# esq.net
KiCad netlist of a schematic drawn in Altium Designer
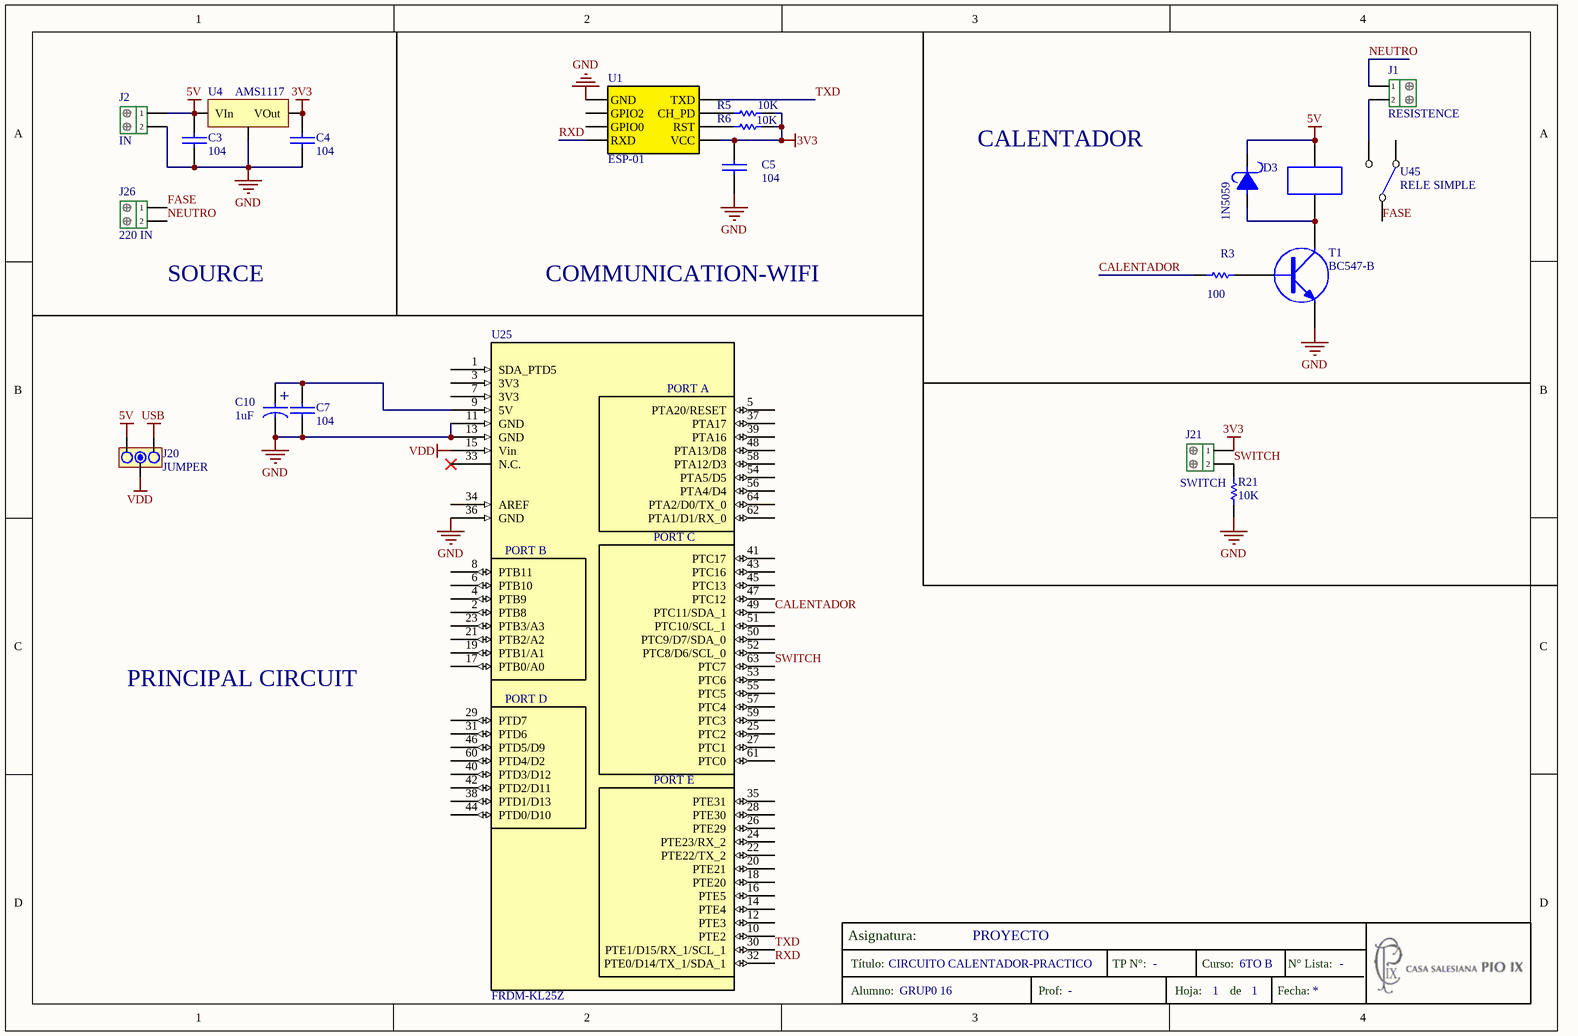
[diagram p0: esq.SchDoc]

(export (version "E")
  (design (tool "Eeschema 10.0.6"))
  (components
    (comp (ref "C3")
      (value "104")
      (footprint "0805")
      (description "cap")
      (fields (field (name "AUTOR") "Guido Spataro"))
      (libsource (lib "Schlib1") (part "CAP"))
    )
    (comp (ref "C4")
      (value "104")
      (footprint "1206")
      (description "cap")
      (fields (field (name "AUTOR") "Guido Spataro"))
      (libsource (lib "Schlib") (part "CAP"))
    )
    (comp (ref "C5")
      (value "104")
      (footprint "0805")
      (description "cap")
      (fields (field (name "AUTOR") "Guido Spataro"))
      (libsource (lib "scdlib") (part "CAP"))
    )
    (comp (ref "C7")
      (value "104")
      (footprint "0805")
      (description "cap")
      (fields (field (name "AUTOR") "Guido Spataro"))
      (libsource (lib "scdlib") (part "CAP"))
    )
    (comp (ref "C10")
      (value "1uF")
      (footprint "CAP100RP")
      (description "Cap polarizado")
      (libsource (lib "Schlib") (part "CAPPOL"))
    )
    (comp (ref "D3")
      (value "1N5059")
      (footprint "Diodo")
      (description "Diodo")
      (fields (field (name "AUTOR") "Guido Spataro"))
      (libsource (lib "Schlib1") (part "DIODO SCHOTTKY"))
    )
    (comp (ref "J1")
      (value "RESISTENCE")
      (footprint "BORNERA2")
      (description "Bornera de 2 pines")
      (fields (field (name "AUTOR") "Guido Spataro"))
      (libsource (lib "Schlib1") (part "Bornera_2"))
    )
    (comp (ref "J2")
      (value "IN")
      (footprint "BORNERA2")
      (description "Bornera de 2 pines")
      (fields (field (name "AUTOR") "Guido Spataro"))
      (libsource (lib "") (part "Bornera_2_1"))
    )
    (comp (ref "J20") (value "JUMPER") (footprint "JUMPER3") (libsource (lib "scdlib") (part "JUMPER3")))
    (comp (ref "J21")
      (value "SWITCH")
      (footprint "BORNERA2")
      (description "Bornera de 2 pines")
      (fields (field (name "AUTOR") "Guido Spataro"))
      (libsource (lib "") (part "Bornera_2_1"))
    )
    (comp (ref "J26")
      (value "220 IN")
      (footprint "BORNERA2")
      (description "Bornera de 2 pines")
      (fields (field (name "AUTOR") "Guido Spataro"))
      (libsource (lib "") (part "Bornera_2_1"))
    )
    (comp (ref "R3")
      (value "100")
      (footprint "0805")
      (description "Resistencia")
      (fields (field (name "AUTOR") "Guido Spataro"))
      (libsource (lib "Schlib1") (part "RES"))
    )
    (comp (ref "R5")
      (value "10K")
      (footprint "0805")
      (description "Resistencia")
      (fields (field (name "AUTOR") "Guido Spataro"))
      (libsource (lib "scdlib") (part "RES"))
    )
    (comp (ref "R6")
      (value "10K")
      (footprint "0805")
      (description "Resistencia")
      (fields (field (name "AUTOR") "Guido Spataro"))
      (libsource (lib "scdlib") (part "RES"))
    )
    (comp (ref "R21")
      (value "10K")
      (footprint "0805")
      (description "Resistencia")
      (fields (field (name "AUTOR") "Guido Spataro"))
      (libsource (lib "Schlib1") (part "RES"))
    )
    (comp (ref "T1")
      (value "BC547-B")
      (footprint "SOT23")
      (libsource (lib "Schlib1") (part "TRANSISTOR NPN"))
    )
    (comp (ref "U1") (value "ESP-01") (footprint "ESP-01") (libsource (lib "Schlib") (part "ESP-01")))
    (comp (ref "U4") (value "AMS1117") (footprint "AMS1117") (libsource (lib "Schlib") (part "AMS1117")))
    (comp (ref "U25")
      (value "FRDM-KL25Z")
      (footprint "MICRO")
      (fields (field (name "AUTOR") "Guido Spataro"))
      (libsource (lib "Schlib") (part "FRDM-KL25Z"))
    )
    (comp (ref "U45")
      (value "RELE SIMPLE")
      (footprint "RELE SERIE 943")
      (libsource (lib "Schlib1") (part "RELE SIMPLE"))
    )
  )
  (nets
    (net (code "1") (name "/CALENTADOR") (class "Default")
      (node (ref "R3") (pin "2") (pinfunction "2_2") (pintype "passive"))
      (node (ref "U25") (pin "49") (pinfunction "PTC11/SDA_1_49") (pintype "bidirectional"))
    )
    (net (code "2") (name "/FASE") (class "Default")
      (node (ref "J26") (pin "1") (pinfunction "1_1") (pintype "passive"))
      (node (ref "U45") (pin "C1") (pinfunction "C1_C1") (pintype "passive"))
    )
    (net (code "3") (name "/NEUTRO") (class "Default")
      (node (ref "J1") (pin "1") (pinfunction "1_1") (pintype "passive"))
      (node (ref "J26") (pin "2") (pinfunction "2_2") (pintype "passive"))
    )
    (net (code "4") (name "/RXD") (class "Default")
      (node (ref "U1") (pin "4") (pinfunction "RXD_4") (pintype "passive"))
      (node (ref "U25") (pin "32") (pinfunction "PTE0/D14/TX_1/SDA_1_32") (pintype "bidirectional"))
    )
    (net (code "5") (name "/SWITCH") (class "Default")
      (node (ref "J21") (pin "2") (pinfunction "2_2") (pintype "passive"))
      (node (ref "R21") (pin "1") (pinfunction "1_1") (pintype "passive"))
      (node (ref "U25") (pin "63") (pinfunction "PTC7_63") (pintype "bidirectional"))
    )
    (net (code "6") (name "/TXD") (class "Default")
      (node (ref "U1") (pin "5") (pinfunction "TXD_5") (pintype "passive"))
      (node (ref "U25") (pin "30") (pinfunction "PTE1/D15/RX_1/SCL_1_30") (pintype "bidirectional"))
    )
    (net (code "7") (name "3V3") (class "Default")
      (node (ref "C4") (pin "1") (pinfunction "1_1") (pintype "passive"))
      (node (ref "C5") (pin "2") (pinfunction "2_2") (pintype "passive"))
      (node (ref "J21") (pin "1") (pinfunction "1_1") (pintype "passive"))
      (node (ref "R5") (pin "1") (pinfunction "1_1") (pintype "passive"))
      (node (ref "R6") (pin "1") (pinfunction "1_1") (pintype "passive"))
      (node (ref "U1") (pin "8") (pinfunction "VCC_8") (pintype "passive"))
      (node (ref "U4") (pin "3") (pinfunction "VOut_3") (pintype "passive"))
    )
    (net (code "8") (name "5V") (class "Default")
      (node (ref "C3") (pin "1") (pinfunction "1_1") (pintype "passive"))
      (node (ref "D3") (pin "2") (pinfunction "2_2") (pintype "passive"))
      (node (ref "J2") (pin "1") (pinfunction "1_1") (pintype "passive"))
      (node (ref "J20") (pin "1") (pinfunction "1_1") (pintype "passive"))
      (node (ref "U4") (pin "1") (pinfunction "VIn_1") (pintype "passive"))
      (node (ref "U45") (pin "B1") (pinfunction "B1_B1") (pintype "passive"))
    )
    (net (code "9") (name "GND") (class "Default")
      (node (ref "C10") (pin "2") (pinfunction "2_2") (pintype "passive"))
      (node (ref "C3") (pin "2") (pinfunction "2_2") (pintype "passive"))
      (node (ref "C4") (pin "2") (pinfunction "2_2") (pintype "passive"))
      (node (ref "C5") (pin "1") (pinfunction "1_1") (pintype "passive"))
      (node (ref "C7") (pin "1") (pinfunction "1_1") (pintype "passive"))
      (node (ref "J2") (pin "2") (pinfunction "2_2") (pintype "passive"))
      (node (ref "R21") (pin "2") (pinfunction "2_2") (pintype "passive"))
      (node (ref "T1") (pin "3") (pinfunction "E_3") (pintype "passive"))
      (node (ref "U1") (pin "1") (pinfunction "GND_1") (pintype "passive"))
      (node (ref "U25") (pin "11") (pinfunction "GND_11") (pintype "input"))
      (node (ref "U25") (pin "13") (pinfunction "GND_13") (pintype "input"))
      (node (ref "U25") (pin "36") (pinfunction "GND_36") (pintype "input"))
      (node (ref "U4") (pin "2") (pinfunction "GND_2") (pintype "passive"))
    )
    (net (code "10") (name "Net-(J1-Pad2)") (class "Default")
      (node (ref "J1") (pin "2") (pinfunction "2_2") (pintype "passive"))
      (node (ref "U45") (pin "NA1") (pinfunction "NA1_NA1") (pintype "passive"))
    )
    (net (code "11") (name "Net-(T1-B)") (class "Default")
      (node (ref "R3") (pin "1") (pinfunction "1_1") (pintype "passive"))
      (node (ref "T1") (pin "1") (pinfunction "B_1") (pintype "passive"))
    )
    (net (code "12") (name "Net-(T1-C)") (class "Default")
      (node (ref "D3") (pin "1") (pinfunction "1_1") (pintype "passive"))
      (node (ref "T1") (pin "2") (pinfunction "C_2") (pintype "passive"))
      (node (ref "U45") (pin "B2") (pinfunction "B2_B2") (pintype "passive"))
    )
    (net (code "13") (name "Net-(U1-CH_PD)") (class "Default")
      (node (ref "R5") (pin "2") (pinfunction "2_2") (pintype "passive"))
      (node (ref "U1") (pin "6") (pinfunction "CH_PD_6") (pintype "passive"))
    )
    (net (code "14") (name "Net-(U1-RST)") (class "Default")
      (node (ref "R6") (pin "2") (pinfunction "2_2") (pintype "passive"))
      (node (ref "U1") (pin "7") (pinfunction "RST_7") (pintype "passive"))
    )
    (net (code "15") (name "Net-(U25-5V)") (class "Default")
      (node (ref "C10") (pin "1") (pinfunction "1_1") (pintype "passive"))
      (node (ref "C7") (pin "2") (pinfunction "2_2") (pintype "passive"))
      (node (ref "U25") (pin "9") (pinfunction "5V_9") (pintype "input"))
    )
    (net (code "16") (name "USB") (class "Default")
      (node (ref "J20") (pin "3") (pinfunction "3_3") (pintype "passive"))
    )
    (net (code "17") (name "VDD") (class "Default")
      (node (ref "J20") (pin "2") (pinfunction "2_2") (pintype "passive"))
      (node (ref "U25") (pin "15") (pinfunction "Vin_15") (pintype "input"))
    )
    (net (code "18") (name "unconnected-(U1-GPIO0-Pad3)") (class "Default")
      (node (ref "U1") (pin "3") (pinfunction "GPIO0_3") (pintype "passive"))
    )
    (net (code "19") (name "unconnected-(U1-GPIO2-Pad2)") (class "Default")
      (node (ref "U1") (pin "2") (pinfunction "GPIO2_2") (pintype "passive"))
    )
    (net (code "20") (name "unconnected-(U25-3V3-Pad3)") (class "Default")
      (node (ref "U25") (pin "3") (pinfunction "3V3_3") (pintype "input"))
    )
    (net (code "21") (name "unconnected-(U25-3V3-Pad7)") (class "Default")
      (node (ref "U25") (pin "7") (pinfunction "3V3_7") (pintype "input"))
    )
    (net (code "22") (name "unconnected-(U25-AREF-Pad34)") (class "Default")
      (node (ref "U25") (pin "34") (pinfunction "AREF_34") (pintype "input"))
    )
    (net (code "23") (name "unconnected-(U25-N.C.-Pad33)") (class "Default")
      (node (ref "U25") (pin "33") (pinfunction "N.C._33") (pintype "open_emitter+no_connect"))
    )
    (net (code "24") (name "unconnected-(U25-PTA1{slash}D1{slash}RX_0-Pad62)") (class "Default")
      (node (ref "U25") (pin "62") (pinfunction "PTA1/D1/RX_0_62") (pintype "bidirectional"))
    )
    (net (code "25") (name "unconnected-(U25-PTA2{slash}D0{slash}TX_0-Pad64)") (class "Default")
      (node (ref "U25") (pin "64") (pinfunction "PTA2/D0/TX_0_64") (pintype "bidirectional"))
    )
    (net (code "26") (name "unconnected-(U25-PTA4{slash}D4-Pad56)") (class "Default")
      (node (ref "U25") (pin "56") (pinfunction "PTA4/D4_56") (pintype "bidirectional"))
    )
    (net (code "27") (name "unconnected-(U25-PTA5{slash}D5-Pad54)") (class "Default")
      (node (ref "U25") (pin "54") (pinfunction "PTA5/D5_54") (pintype "bidirectional"))
    )
    (net (code "28") (name "unconnected-(U25-PTA12{slash}D3-Pad58)") (class "Default")
      (node (ref "U25") (pin "58") (pinfunction "PTA12/D3_58") (pintype "bidirectional"))
    )
    (net (code "29") (name "unconnected-(U25-PTA13{slash}D8-Pad48)") (class "Default")
      (node (ref "U25") (pin "48") (pinfunction "PTA13/D8_48") (pintype "bidirectional"))
    )
    (net (code "30") (name "unconnected-(U25-PTA16-Pad39)") (class "Default")
      (node (ref "U25") (pin "39") (pinfunction "PTA16_39") (pintype "bidirectional"))
    )
    (net (code "31") (name "unconnected-(U25-PTA17-Pad37)") (class "Default")
      (node (ref "U25") (pin "37") (pinfunction "PTA17_37") (pintype "bidirectional"))
    )
    (net (code "32") (name "unconnected-(U25-PTA20{slash}RESET-Pad5)") (class "Default")
      (node (ref "U25") (pin "5") (pinfunction "PTA20/RESET_5") (pintype "bidirectional"))
    )
    (net (code "33") (name "unconnected-(U25-PTB0{slash}A0-Pad17)") (class "Default")
      (node (ref "U25") (pin "17") (pinfunction "PTB0/A0_17") (pintype "bidirectional"))
    )
    (net (code "34") (name "unconnected-(U25-PTB1{slash}A1-Pad19)") (class "Default")
      (node (ref "U25") (pin "19") (pinfunction "PTB1/A1_19") (pintype "bidirectional"))
    )
    (net (code "35") (name "unconnected-(U25-PTB2{slash}A2-Pad21)") (class "Default")
      (node (ref "U25") (pin "21") (pinfunction "PTB2/A2_21") (pintype "bidirectional"))
    )
    (net (code "36") (name "unconnected-(U25-PTB3{slash}A3-Pad23)") (class "Default")
      (node (ref "U25") (pin "23") (pinfunction "PTB3/A3_23") (pintype "bidirectional"))
    )
    (net (code "37") (name "unconnected-(U25-PTB8-Pad2)") (class "Default")
      (node (ref "U25") (pin "2") (pinfunction "PTB8_2") (pintype "bidirectional"))
    )
    (net (code "38") (name "unconnected-(U25-PTB9-Pad4)") (class "Default")
      (node (ref "U25") (pin "4") (pinfunction "PTB9_4") (pintype "bidirectional"))
    )
    (net (code "39") (name "unconnected-(U25-PTB10-Pad6)") (class "Default")
      (node (ref "U25") (pin "6") (pinfunction "PTB10_6") (pintype "bidirectional"))
    )
    (net (code "40") (name "unconnected-(U25-PTB11-Pad8)") (class "Default")
      (node (ref "U25") (pin "8") (pinfunction "PTB11_8") (pintype "bidirectional"))
    )
    (net (code "41") (name "unconnected-(U25-PTC0-Pad61)") (class "Default")
      (node (ref "U25") (pin "61") (pinfunction "PTC0_61") (pintype "bidirectional"))
    )
    (net (code "42") (name "unconnected-(U25-PTC1-Pad27)") (class "Default")
      (node (ref "U25") (pin "27") (pinfunction "PTC1_27") (pintype "bidirectional"))
    )
    (net (code "43") (name "unconnected-(U25-PTC2-Pad25)") (class "Default")
      (node (ref "U25") (pin "25") (pinfunction "PTC2_25") (pintype "bidirectional"))
    )
    (net (code "44") (name "unconnected-(U25-PTC3-Pad59)") (class "Default")
      (node (ref "U25") (pin "59") (pinfunction "PTC3_59") (pintype "bidirectional"))
    )
    (net (code "45") (name "unconnected-(U25-PTC4-Pad57)") (class "Default")
      (node (ref "U25") (pin "57") (pinfunction "PTC4_57") (pintype "bidirectional"))
    )
    (net (code "46") (name "unconnected-(U25-PTC5-Pad55)") (class "Default")
      (node (ref "U25") (pin "55") (pinfunction "PTC5_55") (pintype "bidirectional"))
    )
    (net (code "47") (name "unconnected-(U25-PTC6-Pad53)") (class "Default")
      (node (ref "U25") (pin "53") (pinfunction "PTC6_53") (pintype "bidirectional"))
    )
    (net (code "48") (name "unconnected-(U25-PTC8{slash}D6{slash}SCL_0-Pad52)") (class "Default")
      (node (ref "U25") (pin "52") (pinfunction "PTC8/D6/SCL_0_52") (pintype "bidirectional"))
    )
    (net (code "49") (name "unconnected-(U25-PTC9{slash}D7{slash}SDA_0-Pad50)") (class "Default")
      (node (ref "U25") (pin "50") (pinfunction "PTC9/D7/SDA_0_50") (pintype "bidirectional"))
    )
    (net (code "50") (name "unconnected-(U25-PTC10{slash}SCL_1-Pad51)") (class "Default")
      (node (ref "U25") (pin "51") (pinfunction "PTC10/SCL_1_51") (pintype "bidirectional"))
    )
    (net (code "51") (name "unconnected-(U25-PTC12-Pad47)") (class "Default")
      (node (ref "U25") (pin "47") (pinfunction "PTC12_47") (pintype "bidirectional"))
    )
    (net (code "52") (name "unconnected-(U25-PTC13-Pad45)") (class "Default")
      (node (ref "U25") (pin "45") (pinfunction "PTC13_45") (pintype "bidirectional"))
    )
    (net (code "53") (name "unconnected-(U25-PTC16-Pad43)") (class "Default")
      (node (ref "U25") (pin "43") (pinfunction "PTC16_43") (pintype "bidirectional"))
    )
    (net (code "54") (name "unconnected-(U25-PTC17-Pad41)") (class "Default")
      (node (ref "U25") (pin "41") (pinfunction "PTC17_41") (pintype "bidirectional"))
    )
    (net (code "55") (name "unconnected-(U25-PTD0{slash}D10-Pad44)") (class "Default")
      (node (ref "U25") (pin "44") (pinfunction "PTD0/D10_44") (pintype "bidirectional"))
    )
    (net (code "56") (name "unconnected-(U25-PTD1{slash}D13-Pad38)") (class "Default")
      (node (ref "U25") (pin "38") (pinfunction "PTD1/D13_38") (pintype "bidirectional"))
    )
    (net (code "57") (name "unconnected-(U25-PTD2{slash}D11-Pad42)") (class "Default")
      (node (ref "U25") (pin "42") (pinfunction "PTD2/D11_42") (pintype "bidirectional"))
    )
    (net (code "58") (name "unconnected-(U25-PTD3{slash}D12-Pad40)") (class "Default")
      (node (ref "U25") (pin "40") (pinfunction "PTD3/D12_40") (pintype "bidirectional"))
    )
    (net (code "59") (name "unconnected-(U25-PTD4{slash}D2-Pad60)") (class "Default")
      (node (ref "U25") (pin "60") (pinfunction "PTD4/D2_60") (pintype "bidirectional"))
    )
    (net (code "60") (name "unconnected-(U25-PTD5{slash}D9-Pad46)") (class "Default")
      (node (ref "U25") (pin "46") (pinfunction "PTD5/D9_46") (pintype "bidirectional"))
    )
    (net (code "61") (name "unconnected-(U25-PTD6-Pad31)") (class "Default")
      (node (ref "U25") (pin "31") (pinfunction "PTD6_31") (pintype "bidirectional"))
    )
    (net (code "62") (name "unconnected-(U25-PTD7-Pad29)") (class "Default")
      (node (ref "U25") (pin "29") (pinfunction "PTD7_29") (pintype "bidirectional"))
    )
    (net (code "63") (name "unconnected-(U25-PTE2-Pad10)") (class "Default")
      (node (ref "U25") (pin "10") (pinfunction "PTE2_10") (pintype "bidirectional"))
    )
    (net (code "64") (name "unconnected-(U25-PTE3-Pad12)") (class "Default")
      (node (ref "U25") (pin "12") (pinfunction "PTE3_12") (pintype "bidirectional"))
    )
    (net (code "65") (name "unconnected-(U25-PTE4-Pad14)") (class "Default")
      (node (ref "U25") (pin "14") (pinfunction "PTE4_14") (pintype "bidirectional"))
    )
    (net (code "66") (name "unconnected-(U25-PTE5-Pad16)") (class "Default")
      (node (ref "U25") (pin "16") (pinfunction "PTE5_16") (pintype "bidirectional"))
    )
    (net (code "67") (name "unconnected-(U25-PTE20-Pad18)") (class "Default")
      (node (ref "U25") (pin "18") (pinfunction "PTE20_18") (pintype "bidirectional"))
    )
    (net (code "68") (name "unconnected-(U25-PTE21-Pad20)") (class "Default")
      (node (ref "U25") (pin "20") (pinfunction "PTE21_20") (pintype "bidirectional"))
    )
    (net (code "69") (name "unconnected-(U25-PTE22{slash}TX_2-Pad22)") (class "Default")
      (node (ref "U25") (pin "22") (pinfunction "PTE22/TX_2_22") (pintype "bidirectional"))
    )
    (net (code "70") (name "unconnected-(U25-PTE23{slash}RX_2-Pad24)") (class "Default")
      (node (ref "U25") (pin "24") (pinfunction "PTE23/RX_2_24") (pintype "bidirectional"))
    )
    (net (code "71") (name "unconnected-(U25-PTE29-Pad26)") (class "Default")
      (node (ref "U25") (pin "26") (pinfunction "PTE29_26") (pintype "bidirectional"))
    )
    (net (code "72") (name "unconnected-(U25-PTE30-Pad28)") (class "Default")
      (node (ref "U25") (pin "28") (pinfunction "PTE30_28") (pintype "bidirectional"))
    )
    (net (code "73") (name "unconnected-(U25-PTE31-Pad35)") (class "Default")
      (node (ref "U25") (pin "35") (pinfunction "PTE31_35") (pintype "bidirectional"))
    )
    (net (code "74") (name "unconnected-(U25-SDA_PTD5-Pad1)") (class "Default")
      (node (ref "U25") (pin "1") (pinfunction "SDA_PTD5_1") (pintype "input"))
    )
    (net (code "75") (name "unconnected-(U45-PadNC1)") (class "Default")
      (node (ref "U45") (pin "NC1") (pinfunction "NC1_NC1") (pintype "passive"))
    )
  )
)
